# driver.net
KiCad netlist of a schematic drawn in EAGLE
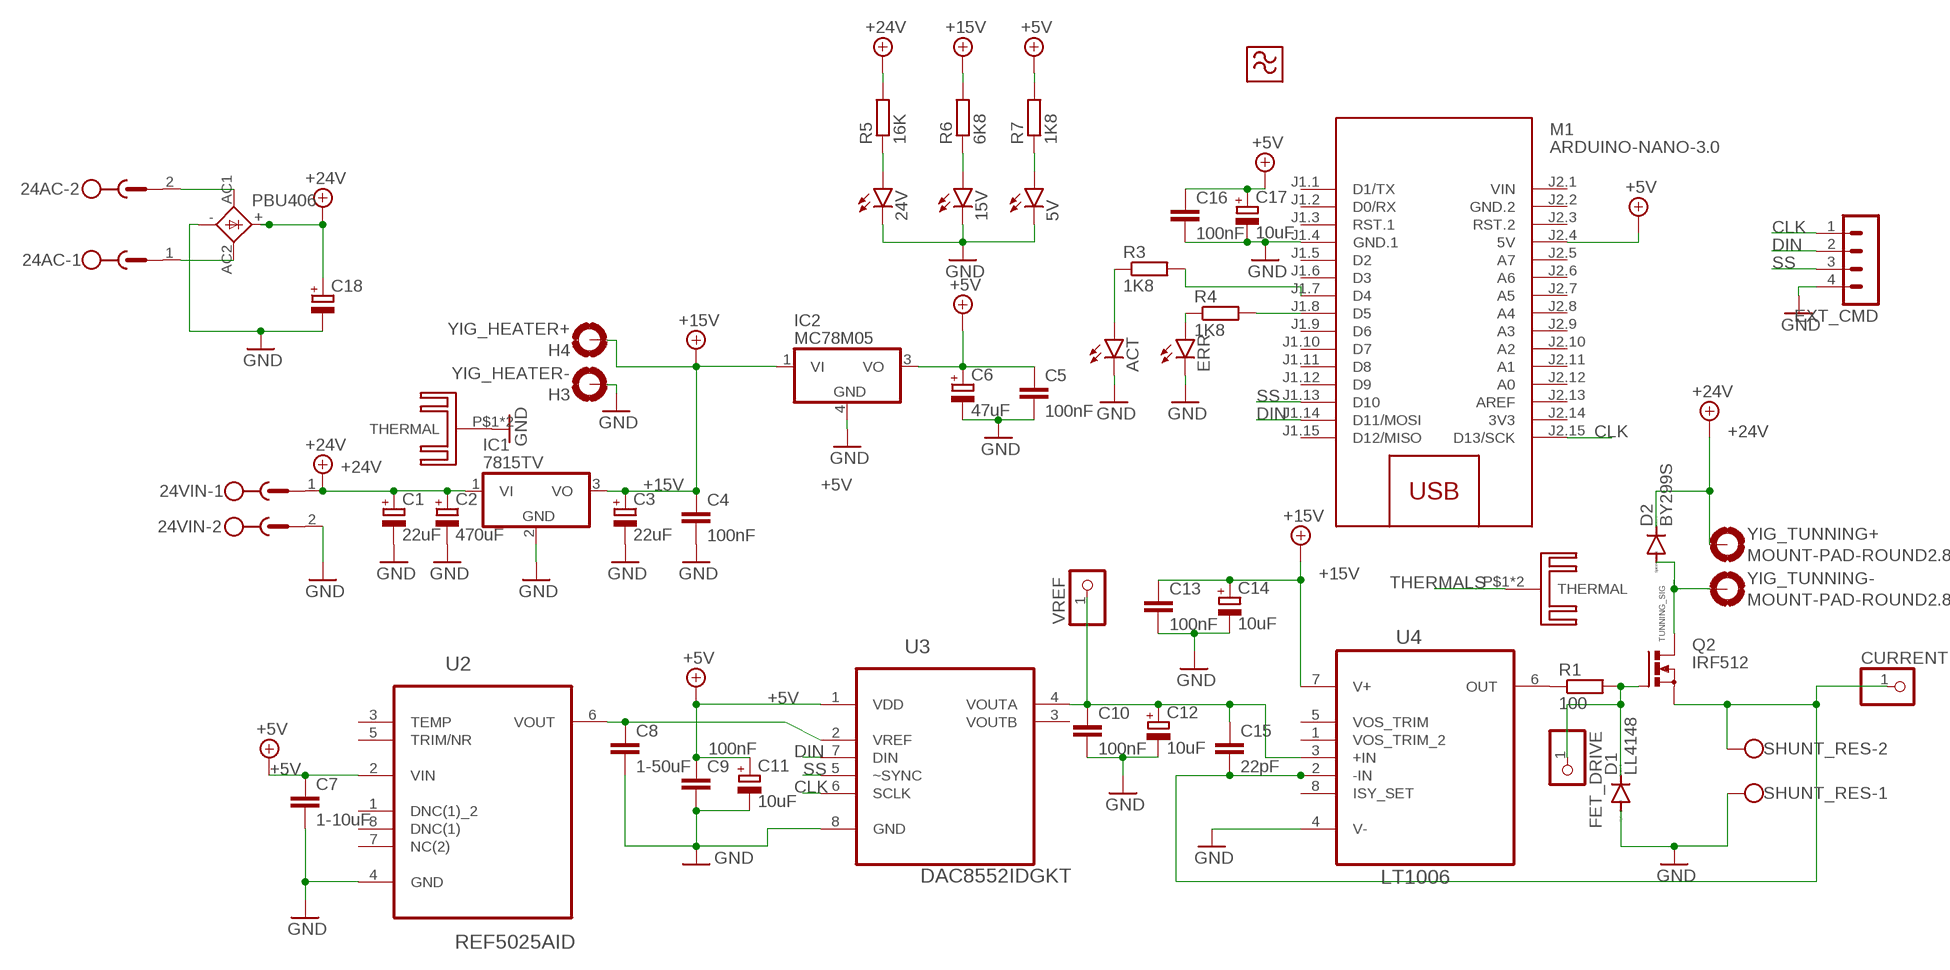
[diagram p0: schematic, sheet 1]

(export (version "E")
  (design (tool "Eeschema 10.0.6"))
  (components
    (comp (ref "5V")
      (value "LEDCHIP-LED0805")
      (footprint "eagle-import:CHIP-LED0805")
      (libsource (lib "eagle-import") (part "LEDCHIP-LED0805"))
    )
    (comp (ref "15V")
      (value "LEDCHIP-LED0805")
      (footprint "eagle-import:CHIP-LED0805")
      (libsource (lib "eagle-import") (part "LEDCHIP-LED0805"))
    )
    (comp (ref "24AC")
      (value "MSTBV2")
      (footprint "eagle-import:MSTBV2")
      (libsource (lib "eagle-import") (part "MSTBV2"))
    )
    (comp (ref "24V")
      (value "LEDCHIP-LED0805")
      (footprint "eagle-import:CHIP-LED0805")
      (libsource (lib "eagle-import") (part "LEDCHIP-LED0805"))
    )
    (comp (ref "24VIN")
      (value "MSTBV2")
      (footprint "eagle-import:MSTBV2")
      (libsource (lib "eagle-import") (part "MSTBV2"))
    )
    (comp (ref "ACT")
      (value "LEDCHIP-LED0805")
      (footprint "eagle-import:CHIP-LED0805")
      (libsource (lib "eagle-import") (part "LEDCHIP-LED0805"))
    )
    (comp (ref "C1")
      (value "22uF")
      (footprint "eagle-import:PANASONIC_E")
      (libsource (lib "eagle-import") (part "CPOL-EUE"))
    )
    (comp (ref "C2")
      (value "470uF")
      (footprint "eagle-import:E5-10,5")
      (libsource (lib "eagle-import") (part "CPOL-EUE5-10.5"))
    )
    (comp (ref "C3")
      (value "22uF")
      (footprint "eagle-import:PANASONIC_E")
      (libsource (lib "eagle-import") (part "CPOL-EUE"))
    )
    (comp (ref "C4")
      (value "100nF")
      (footprint "eagle-import:C1210")
      (libsource (lib "eagle-import") (part "C-EUC1210"))
    )
    (comp (ref "C5")
      (value "100nF")
      (footprint "eagle-import:C0603K")
      (libsource (lib "eagle-import") (part "C-EUC0603K"))
    )
    (comp (ref "C6")
      (value "47uF")
      (footprint "eagle-import:PANASONIC_D")
      (libsource (lib "eagle-import") (part "CPOL-EUD"))
    )
    (comp (ref "C7")
      (value "1-10uF")
      (footprint "eagle-import:C3216")
      (libsource (lib "eagle-import") (part "C-EUC3216"))
    )
    (comp (ref "C8")
      (value "1-50uF")
      (footprint "eagle-import:C3216")
      (libsource (lib "eagle-import") (part "C-EUC3216"))
    )
    (comp (ref "C9")
      (value "100nF")
      (footprint "eagle-import:C0603K")
      (libsource (lib "eagle-import") (part "C-EUC0603K"))
    )
    (comp (ref "C10")
      (value "100nF")
      (footprint "eagle-import:C0603K")
      (libsource (lib "eagle-import") (part "C-EUC0603K"))
    )
    (comp (ref "C11")
      (value "10uF")
      (footprint "eagle-import:A_3216-18R")
      (libsource (lib "eagle-import") (part "CPOL-EUA/3216-18R"))
    )
    (comp (ref "C12")
      (value "10uF")
      (footprint "eagle-import:A_3216-18R")
      (libsource (lib "eagle-import") (part "CPOL-EUA/3216-18R"))
    )
    (comp (ref "C13")
      (value "100nF")
      (footprint "eagle-import:C1210")
      (libsource (lib "eagle-import") (part "C-EUC1210"))
    )
    (comp (ref "C14")
      (value "10uF")
      (footprint "eagle-import:E2,5-5")
      (libsource (lib "eagle-import") (part "CPOL-EUE2.5-5"))
    )
    (comp (ref "C15")
      (value "22pF")
      (footprint "eagle-import:C0603")
      (libsource (lib "eagle-import") (part "C-EUC0603"))
    )
    (comp (ref "C16")
      (value "100nF")
      (footprint "eagle-import:C0603K")
      (libsource (lib "eagle-import") (part "C-EUC0603K"))
    )
    (comp (ref "C17")
      (value "10uF")
      (footprint "eagle-import:A_3216-18R")
      (libsource (lib "eagle-import") (part "CPOL-EUA/3216-18R"))
    )
    (comp (ref "C18")
      (value "CPOL-EUE7.5-18")
      (footprint "eagle-import:E7,5-18")
      (libsource (lib "eagle-import") (part "CPOL-EUE7.5-18"))
    )
    (comp (ref "CURRENT")
      (value "PINHD-1X1")
      (footprint "eagle-import:1X01")
      (libsource (lib "eagle-import") (part "PINHD-1X1"))
    )
    (comp (ref "D1")
      (value "LL4148")
      (footprint "eagle-import:SOD80C")
      (libsource (lib "eagle-import") (part "DIODE-SOD80C"))
    )
    (comp (ref "D2")
      (value "BY299S")
      (footprint "eagle-import:D-10")
      (libsource (lib "eagle-import") (part "DIODE-D-10"))
    )
    (comp (ref "ERR")
      (value "LEDCHIP-LED0805")
      (footprint "eagle-import:CHIP-LED0805")
      (libsource (lib "eagle-import") (part "LEDCHIP-LED0805"))
    )
    (comp (ref "EXT_CMD")
      (value "MA04-1")
      (footprint "eagle-import:MA04-1")
      (libsource (lib "eagle-import") (part "MA04-1"))
    )
    (comp (ref "FET_DRIVE")
      (value "PINHD-1X1")
      (footprint "eagle-import:1X01")
      (libsource (lib "eagle-import") (part "PINHD-1X1"))
    )
    (comp (ref "H3")
      (value "YIG_HEATER-")
      (footprint "eagle-import:2,8-PAD")
      (libsource (lib "eagle-import") (part "MOUNT-PAD-ROUND2.8"))
    )
    (comp (ref "H4")
      (value "YIG_HEATER+")
      (footprint "eagle-import:2,8-PAD")
      (libsource (lib "eagle-import") (part "MOUNT-PAD-ROUND2.8"))
    )
    (comp (ref "HEATSYNK")
      (value "SK09/20V")
      (footprint "eagle-import:SK09_20V")
      (libsource (lib "eagle-import") (part "SK09/20V"))
    )
    (comp (ref "IC1")
      (value "7815TV")
      (footprint "eagle-import:TO220V")
      (libsource (lib "eagle-import") (part "78TV15"))
    )
    (comp (ref "IC2")
      (value "MC78M05")
      (footprint "eagle-import:DPACK_3")
      (libsource (lib "eagle-import") (part "MC78M05CDTG"))
    )
    (comp (ref "M1")
      (value "ARDUINO-NANO-3.0")
      (footprint "eagle-import:ARDUINO-NANO-3.0")
      (libsource (lib "eagle-import") (part "ARDUINO-NANO-3.0"))
    )
    (comp (ref "PBU406")
      (value "2KBP2KBP_MINE")
      (footprint "eagle-import:2KBP_MINE")
      (libsource (lib "eagle-import") (part "2KBP2KBP_MINE"))
    )
    (comp (ref "Q2")
      (value "IRF512")
      (footprint "eagle-import:TO220BV")
      (libsource (lib "eagle-import") (part "IRF512"))
    )
    (comp (ref "R1")
      (value "100")
      (footprint "eagle-import:M0805")
      (libsource (lib "eagle-import") (part "R-EU_M0805"))
    )
    (comp (ref "R3")
      (value "1K8")
      (footprint "eagle-import:M0805")
      (libsource (lib "eagle-import") (part "resistor_348_R-EU_M0805"))
    )
    (comp (ref "R4")
      (value "1K8")
      (footprint "eagle-import:M0805")
      (libsource (lib "eagle-import") (part "resistor_348_R-EU_M0805"))
    )
    (comp (ref "R5")
      (value "16K")
      (footprint "eagle-import:M0805")
      (libsource (lib "eagle-import") (part "resistor_348_R-EU_M0805"))
    )
    (comp (ref "R6")
      (value "6K8")
      (footprint "eagle-import:M0805")
      (libsource (lib "eagle-import") (part "resistor_348_R-EU_M0805"))
    )
    (comp (ref "R7")
      (value "1K8")
      (footprint "eagle-import:M0805")
      (libsource (lib "eagle-import") (part "resistor_348_R-EU_M0805"))
    )
    (comp (ref "SHUNT_RES")
      (value "W237-102")
      (footprint "eagle-import:W237-102")
      (fields (field (name "MPN") "237-102"))
      (libsource (lib "eagle-import") (part "W237-102"))
    )
    (comp (ref "U$1")
      (value "SK09/20V")
      (footprint "eagle-import:SK09_20V")
      (libsource (lib "eagle-import") (part "SK09/20V"))
    )
    (comp (ref "U$2")
      (value "YIG_FILTER")
      (footprint "eagle-import:EBAY")
      (libsource (lib "eagle-import") (part "YIG_FILTER"))
    )
    (comp (ref "U2")
      (value "REF5025AID")
      (footprint "eagle-import:SOIC127P600X175-8N")
      (libsource (lib "eagle-import") (part "REF5025AID"))
    )
    (comp (ref "U3")
      (value "DAC8552IDGKT")
      (footprint "eagle-import:SOP65P490X110-8N")
      (libsource (lib "eagle-import") (part "DAC8552IDGKT"))
    )
    (comp (ref "U4")
      (value "LT1006")
      (footprint "eagle-import:SOIC127P600X175-8N")
      (fields (field (name "MPN") "LT1006S8#PBF"))
      (libsource (lib "eagle-import") (part "LT1006S8PBF"))
    )
    (comp (ref "VREF")
      (value "PINHD-1X1")
      (footprint "eagle-import:1X01")
      (libsource (lib "eagle-import") (part "PINHD-1X1"))
    )
    (comp (ref "YIG_TUNNING+")
      (value "MOUNT-PAD-ROUND2.8")
      (footprint "eagle-import:2,8-PAD")
      (libsource (lib "eagle-import") (part "MOUNT-PAD-ROUND2.8"))
    )
    (comp (ref "YIG_TUNNING-")
      (value "MOUNT-PAD-ROUND2.8")
      (footprint "eagle-import:2,8-PAD")
      (libsource (lib "eagle-import") (part "MOUNT-PAD-ROUND2.8"))
    )
  )
  (nets
    (net (code "1") (name "+5V") (class "Default")
      (node (ref "C11") (pin "+") (pinfunction "+_+") (pintype "passive"))
      (node (ref "C16") (pin "1") (pinfunction "1_1") (pintype "passive"))
      (node (ref "C17") (pin "+") (pinfunction "+_+") (pintype "passive"))
      (node (ref "C5") (pin "1") (pinfunction "1_1") (pintype "passive"))
      (node (ref "C6") (pin "+") (pinfunction "+_+") (pintype "passive"))
      (node (ref "C7") (pin "1") (pinfunction "1_1") (pintype "passive"))
      (node (ref "C9") (pin "1") (pinfunction "1_1") (pintype "passive"))
      (node (ref "IC2") (pin "3") (pinfunction "VO_3") (pintype "passive"))
      (node (ref "M1") (pin "J2.4") (pinfunction "5V_J2.4") (pintype "power_in"))
      (node (ref "R7") (pin "2") (pinfunction "2_2") (pintype "passive"))
      (node (ref "U2") (pin "2") (pinfunction "VIN_2") (pintype "input"))
      (node (ref "U3") (pin "1") (pinfunction "VDD_1") (pintype "power_in"))
    )
    (net (code "2") (name "+15V") (class "Default")
      (node (ref "C13") (pin "1") (pinfunction "1_1") (pintype "passive"))
      (node (ref "C14") (pin "+") (pinfunction "+_+") (pintype "passive"))
      (node (ref "C3") (pin "+") (pinfunction "+_+") (pintype "passive"))
      (node (ref "C4") (pin "1") (pinfunction "1_1") (pintype "passive"))
      (node (ref "H4") (pin "B2,8") (pinfunction "MOUNT_B2,8") (pintype "passive"))
      (node (ref "IC1") (pin "3") (pinfunction "VO_3") (pintype "passive"))
      (node (ref "IC2") (pin "1") (pinfunction "VI_1") (pintype "input"))
      (node (ref "R6") (pin "2") (pinfunction "2_2") (pintype "passive"))
      (node (ref "U4") (pin "7") (pinfunction "V+_7") (pintype "power_in"))
    )
    (net (code "3") (name "+24V") (class "Default")
      (node (ref "24VIN") (pin "1") (pinfunction "SK_1") (pintype "passive"))
      (node (ref "C1") (pin "+") (pinfunction "+_+") (pintype "passive"))
      (node (ref "C18") (pin "+") (pinfunction "+_+") (pintype "passive"))
      (node (ref "C2") (pin "+") (pinfunction "+_+") (pintype "passive"))
      (node (ref "D2") (pin "C") (pinfunction "C_C") (pintype "passive"))
      (node (ref "IC1") (pin "1") (pinfunction "VI_1") (pintype "input"))
      (node (ref "PBU406") (pin "+") (pinfunction "+_+") (pintype "passive"))
      (node (ref "R5") (pin "2") (pinfunction "2_2") (pintype "passive"))
      (node (ref "YIG_TUNNING+") (pin "B2,8") (pinfunction "MOUNT_B2,8") (pintype "passive"))
    )
    (net (code "4") (name "/3V3") (class "Default")
      (node (ref "M1") (pin "J2.14") (pinfunction "3V3_J2.14") (pintype "power_in"))
    )
    (net (code "5") (name "/CLK") (class "Default")
      (node (ref "EXT_CMD") (pin "1") (pinfunction "1_1") (pintype "passive"))
      (node (ref "M1") (pin "J2.15") (pinfunction "D13/SCK_J2.15") (pintype "bidirectional"))
      (node (ref "U3") (pin "6") (pinfunction "SCLK_6") (pintype "input"))
    )
    (net (code "6") (name "/DIN") (class "Default")
      (node (ref "EXT_CMD") (pin "2") (pinfunction "2_2") (pintype "passive"))
      (node (ref "M1") (pin "J1.14") (pinfunction "D11/MOSI_J1.14") (pintype "bidirectional"))
      (node (ref "U3") (pin "7") (pinfunction "DIN_7") (pintype "input"))
    )
    (net (code "7") (name "/GND.2") (class "Default")
      (node (ref "M1") (pin "J2.2") (pinfunction "GND.2_J2.2") (pintype "power_in"))
    )
    (net (code "8") (name "/SS") (class "Default")
      (node (ref "EXT_CMD") (pin "3") (pinfunction "3_3") (pintype "passive"))
      (node (ref "M1") (pin "J1.13") (pinfunction "D10_J1.13") (pintype "bidirectional"))
      (node (ref "U3") (pin "5") (pinfunction "~{SYNC}_5") (pintype "input"))
    )
    (net (code "9") (name "/THERMALS") (class "Default")
      (node (ref "U$1") (pin "P$1") (pinfunction "THERMAL_P$1") (pintype "bidirectional"))
      (node (ref "U$1") (pin "P$2") (pinfunction "THERMAL_P$2") (pintype "bidirectional"))
    )
    (net (code "10") (name "/TUNNING_SIG") (class "Default")
      (node (ref "D2") (pin "A") (pinfunction "A_A") (pintype "passive"))
      (node (ref "Q2") (pin "D") (pinfunction "D_D") (pintype "passive"))
      (node (ref "YIG_TUNNING-") (pin "B2,8") (pinfunction "MOUNT_B2,8") (pintype "passive"))
    )
    (net (code "11") (name "/VIN") (class "Default")
      (node (ref "M1") (pin "J2.1") (pinfunction "VIN_J2.1") (pintype "power_in"))
    )
    (net (code "12") (name "GND") (class "Default")
      (node (ref "15V") (pin "C") (pinfunction "C_C") (pintype "passive"))
      (node (ref "24V") (pin "C") (pinfunction "C_C") (pintype "passive"))
      (node (ref "24VIN") (pin "2") (pinfunction "SK_2") (pintype "passive"))
      (node (ref "5V") (pin "C") (pinfunction "C_C") (pintype "passive"))
      (node (ref "ACT") (pin "C") (pinfunction "C_C") (pintype "passive"))
      (node (ref "C1") (pin "-") (pinfunction "-_-") (pintype "passive"))
      (node (ref "C10") (pin "2") (pinfunction "2_2") (pintype "passive"))
      (node (ref "C11") (pin "-") (pinfunction "-_-") (pintype "passive"))
      (node (ref "C12") (pin "-") (pinfunction "-_-") (pintype "passive"))
      (node (ref "C13") (pin "2") (pinfunction "2_2") (pintype "passive"))
      (node (ref "C14") (pin "-") (pinfunction "-_-") (pintype "passive"))
      (node (ref "C16") (pin "2") (pinfunction "2_2") (pintype "passive"))
      (node (ref "C17") (pin "-") (pinfunction "-_-") (pintype "passive"))
      (node (ref "C18") (pin "-") (pinfunction "-_-") (pintype "passive"))
      (node (ref "C2") (pin "-") (pinfunction "-_-") (pintype "passive"))
      (node (ref "C3") (pin "-") (pinfunction "-_-") (pintype "passive"))
      (node (ref "C4") (pin "2") (pinfunction "2_2") (pintype "passive"))
      (node (ref "C5") (pin "2") (pinfunction "2_2") (pintype "passive"))
      (node (ref "C6") (pin "-") (pinfunction "-_-") (pintype "passive"))
      (node (ref "C7") (pin "2") (pinfunction "2_2") (pintype "passive"))
      (node (ref "C8") (pin "2") (pinfunction "2_2") (pintype "passive"))
      (node (ref "C9") (pin "2") (pinfunction "2_2") (pintype "passive"))
      (node (ref "D1") (pin "A") (pinfunction "A_A") (pintype "passive"))
      (node (ref "ERR") (pin "C") (pinfunction "C_C") (pintype "passive"))
      (node (ref "EXT_CMD") (pin "4") (pinfunction "4_4") (pintype "passive"))
      (node (ref "H3") (pin "B2,8") (pinfunction "MOUNT_B2,8") (pintype "passive"))
      (node (ref "HEATSYNK") (pin "P$1") (pinfunction "THERMAL_P$1") (pintype "bidirectional"))
      (node (ref "HEATSYNK") (pin "P$2") (pinfunction "THERMAL_P$2") (pintype "bidirectional"))
      (node (ref "IC1") (pin "2") (pinfunction "GND_2") (pintype "passive"))
      (node (ref "IC2") (pin "4") (pinfunction "GND_4") (pintype "passive"))
      (node (ref "M1") (pin "J1.4") (pinfunction "GND.1_J1.4") (pintype "power_in"))
      (node (ref "PBU406") (pin "-") (pinfunction "-_-") (pintype "passive"))
      (node (ref "SHUNT_RES") (pin "1") (pinfunction "KL_1") (pintype "passive"))
      (node (ref "U2") (pin "4") (pinfunction "GND_4") (pintype "passive"))
      (node (ref "U3") (pin "8") (pinfunction "GND_8") (pintype "passive"))
      (node (ref "U4") (pin "4") (pinfunction "V-_4") (pintype "power_in"))
    )
    (net (code "13") (name "Net-(5V-PadA)") (class "Default")
      (node (ref "5V") (pin "A") (pinfunction "A_A") (pintype "passive"))
      (node (ref "R7") (pin "1") (pinfunction "1_1") (pintype "passive"))
    )
    (net (code "14") (name "Net-(15V-PadA)") (class "Default")
      (node (ref "15V") (pin "A") (pinfunction "A_A") (pintype "passive"))
      (node (ref "R6") (pin "1") (pinfunction "1_1") (pintype "passive"))
    )
    (net (code "15") (name "Net-(24ACA-SK)") (class "Default")
      (node (ref "24AC") (pin "1") (pinfunction "SK_1") (pintype "passive"))
      (node (ref "PBU406") (pin "AC2") (pinfunction "AC2_AC2") (pintype "passive"))
    )
    (net (code "16") (name "Net-(24ACB-SK)") (class "Default")
      (node (ref "24AC") (pin "2") (pinfunction "SK_2") (pintype "passive"))
      (node (ref "PBU406") (pin "AC1") (pinfunction "AC1_AC1") (pintype "passive"))
    )
    (net (code "17") (name "Net-(24V-PadA)") (class "Default")
      (node (ref "24V") (pin "A") (pinfunction "A_A") (pintype "passive"))
      (node (ref "R5") (pin "1") (pinfunction "1_1") (pintype "passive"))
    )
    (net (code "18") (name "Net-(ACT-PadA)") (class "Default")
      (node (ref "ACT") (pin "A") (pinfunction "A_A") (pintype "passive"))
      (node (ref "R3") (pin "1") (pinfunction "1_1") (pintype "passive"))
    )
    (net (code "19") (name "Net-(D1-PadC)") (class "Default")
      (node (ref "D1") (pin "C") (pinfunction "C_C") (pintype "passive"))
      (node (ref "FET_DRIVE") (pin "1") (pinfunction "1_1") (pintype "passive"))
      (node (ref "Q2") (pin "G") (pinfunction "G_G") (pintype "passive"))
      (node (ref "R1") (pin "2") (pinfunction "2_2") (pintype "passive"))
    )
    (net (code "20") (name "Net-(ERR-PadA)") (class "Default")
      (node (ref "ERR") (pin "A") (pinfunction "A_A") (pintype "passive"))
      (node (ref "R4") (pin "1") (pinfunction "1_1") (pintype "passive"))
    )
    (net (code "21") (name "Net-(M1-D4)") (class "Default")
      (node (ref "M1") (pin "J1.7") (pinfunction "D4_J1.7") (pintype "bidirectional"))
      (node (ref "R3") (pin "2") (pinfunction "2_2") (pintype "passive"))
    )
    (net (code "22") (name "Net-(M1-D5)") (class "Default")
      (node (ref "M1") (pin "J1.8") (pinfunction "D5_J1.8") (pintype "bidirectional"))
      (node (ref "R4") (pin "2") (pinfunction "2_2") (pintype "passive"))
    )
    (net (code "23") (name "Net-(SHUNT_RESB-KL)") (class "Default")
      (node (ref "C15") (pin "2") (pinfunction "2_2") (pintype "passive"))
      (node (ref "CURRENT") (pin "1") (pinfunction "1_1") (pintype "passive"))
      (node (ref "Q2") (pin "S") (pinfunction "S_S") (pintype "passive"))
      (node (ref "SHUNT_RES") (pin "2") (pinfunction "KL_2") (pintype "passive"))
      (node (ref "U4") (pin "2") (pinfunction "-IN_2") (pintype "input"))
    )
    (net (code "24") (name "Net-(U2-VOUT)") (class "Default")
      (node (ref "C8") (pin "1") (pinfunction "1_1") (pintype "passive"))
      (node (ref "U2") (pin "6") (pinfunction "VOUT_6") (pintype "output"))
      (node (ref "U3") (pin "2") (pinfunction "VREF_2") (pintype "input"))
    )
    (net (code "25") (name "Net-(U3-VOUTA)") (class "Default")
      (node (ref "C10") (pin "1") (pinfunction "1_1") (pintype "passive"))
      (node (ref "C12") (pin "+") (pinfunction "+_+") (pintype "passive"))
      (node (ref "C15") (pin "1") (pinfunction "1_1") (pintype "passive"))
      (node (ref "U3") (pin "4") (pinfunction "VOUTA_4") (pintype "output"))
      (node (ref "U4") (pin "3") (pinfunction "+IN_3") (pintype "input"))
      (node (ref "VREF") (pin "1") (pinfunction "1_1") (pintype "passive"))
    )
    (net (code "26") (name "Net-(U4-OUT)") (class "Default")
      (node (ref "R1") (pin "1") (pinfunction "1_1") (pintype "passive"))
      (node (ref "U4") (pin "6") (pinfunction "OUT_6") (pintype "output"))
    )
    (net (code "27") (name "unconnected-(M1-A0-PadJ2.12)") (class "Default")
      (node (ref "M1") (pin "J2.12") (pinfunction "A0_J2.12") (pintype "bidirectional"))
    )
    (net (code "28") (name "unconnected-(M1-A1-PadJ2.11)") (class "Default")
      (node (ref "M1") (pin "J2.11") (pinfunction "A1_J2.11") (pintype "bidirectional"))
    )
    (net (code "29") (name "unconnected-(M1-A2-PadJ2.10)") (class "Default")
      (node (ref "M1") (pin "J2.10") (pinfunction "A2_J2.10") (pintype "bidirectional"))
    )
    (net (code "30") (name "unconnected-(M1-A3-PadJ2.9)") (class "Default")
      (node (ref "M1") (pin "J2.9") (pinfunction "A3_J2.9") (pintype "bidirectional"))
    )
    (net (code "31") (name "unconnected-(M1-A4-PadJ2.8)") (class "Default")
      (node (ref "M1") (pin "J2.8") (pinfunction "A4_J2.8") (pintype "bidirectional"))
    )
    (net (code "32") (name "unconnected-(M1-A5-PadJ2.7)") (class "Default")
      (node (ref "M1") (pin "J2.7") (pinfunction "A5_J2.7") (pintype "bidirectional"))
    )
    (net (code "33") (name "unconnected-(M1-A6-PadJ2.6)") (class "Default")
      (node (ref "M1") (pin "J2.6") (pinfunction "A6_J2.6") (pintype "bidirectional"))
    )
    (net (code "34") (name "unconnected-(M1-A7-PadJ2.5)") (class "Default")
      (node (ref "M1") (pin "J2.5") (pinfunction "A7_J2.5") (pintype "bidirectional"))
    )
    (net (code "35") (name "unconnected-(M1-AREF-PadJ2.13)") (class "Default")
      (node (ref "M1") (pin "J2.13") (pinfunction "AREF_J2.13") (pintype "bidirectional"))
    )
    (net (code "36") (name "unconnected-(M1-D0{slash}RX-PadJ1.2)") (class "Default")
      (node (ref "M1") (pin "J1.2") (pinfunction "D0/RX_J1.2") (pintype "bidirectional"))
    )
    (net (code "37") (name "unconnected-(M1-D1{slash}TX-PadJ1.1)") (class "Default")
      (node (ref "M1") (pin "J1.1") (pinfunction "D1/TX_J1.1") (pintype "bidirectional"))
    )
    (net (code "38") (name "unconnected-(M1-D2-PadJ1.5)") (class "Default")
      (node (ref "M1") (pin "J1.5") (pinfunction "D2_J1.5") (pintype "bidirectional"))
    )
    (net (code "39") (name "unconnected-(M1-D3-PadJ1.6)") (class "Default")
      (node (ref "M1") (pin "J1.6") (pinfunction "D3_J1.6") (pintype "bidirectional"))
    )
    (net (code "40") (name "unconnected-(M1-D6-PadJ1.9)") (class "Default")
      (node (ref "M1") (pin "J1.9") (pinfunction "D6_J1.9") (pintype "bidirectional"))
    )
    (net (code "41") (name "unconnected-(M1-D7-PadJ1.10)") (class "Default")
      (node (ref "M1") (pin "J1.10") (pinfunction "D7_J1.10") (pintype "bidirectional"))
    )
    (net (code "42") (name "unconnected-(M1-D8-PadJ1.11)") (class "Default")
      (node (ref "M1") (pin "J1.11") (pinfunction "D8_J1.11") (pintype "bidirectional"))
    )
    (net (code "43") (name "unconnected-(M1-D9-PadJ1.12)") (class "Default")
      (node (ref "M1") (pin "J1.12") (pinfunction "D9_J1.12") (pintype "bidirectional"))
    )
    (net (code "44") (name "unconnected-(M1-D12{slash}MISO-PadJ1.15)") (class "Default")
      (node (ref "M1") (pin "J1.15") (pinfunction "D12/MISO_J1.15") (pintype "bidirectional"))
    )
    (net (code "45") (name "unconnected-(M1-RST.1-PadJ1.3)") (class "Default")
      (node (ref "M1") (pin "J1.3") (pinfunction "RST.1_J1.3") (pintype "bidirectional"))
    )
    (net (code "46") (name "unconnected-(M1-RST.2-PadJ2.3)") (class "Default")
      (node (ref "M1") (pin "J2.3") (pinfunction "RST.2_J2.3") (pintype "bidirectional"))
    )
    (net (code "47") (name "unconnected-(U2-DNC(1)-Pad8)") (class "Default")
      (node (ref "U2") (pin "8") (pinfunction "DNC(1)_8") (pintype "no_connect"))
    )
    (net (code "48") (name "unconnected-(U2-DNC(1)_2-Pad1)") (class "Default")
      (node (ref "U2") (pin "1") (pinfunction "DNC(1)_2_1") (pintype "no_connect"))
    )
    (net (code "49") (name "unconnected-(U2-NC(2)-Pad7)") (class "Default")
      (node (ref "U2") (pin "7") (pinfunction "NC(2)_7") (pintype "no_connect"))
    )
    (net (code "50") (name "unconnected-(U2-TEMP-Pad3)") (class "Default")
      (node (ref "U2") (pin "3") (pinfunction "TEMP_3") (pintype "input"))
    )
    (net (code "51") (name "unconnected-(U2-TRIM{slash}NR-Pad5)") (class "Default")
      (node (ref "U2") (pin "5") (pinfunction "TRIM/NR_5") (pintype "input"))
    )
    (net (code "52") (name "unconnected-(U3-VOUTB-Pad3)") (class "Default")
      (node (ref "U3") (pin "3") (pinfunction "VOUTB_3") (pintype "output"))
    )
    (net (code "53") (name "unconnected-(U4-ISY_SET-Pad8)") (class "Default")
      (node (ref "U4") (pin "8") (pinfunction "ISY_SET_8") (pintype "input"))
    )
    (net (code "54") (name "unconnected-(U4-VOS_TRIM-Pad5)") (class "Default")
      (node (ref "U4") (pin "5") (pinfunction "VOS_TRIM_5") (pintype "passive"))
    )
    (net (code "55") (name "unconnected-(U4-VOS_TRIM_2-Pad1)") (class "Default")
      (node (ref "U4") (pin "1") (pinfunction "VOS_TRIM_2_1") (pintype "passive"))
    )
  )
)
